# UVBoardFlippingGND.net
KiCad netlist of a schematic drawn in EAGLE
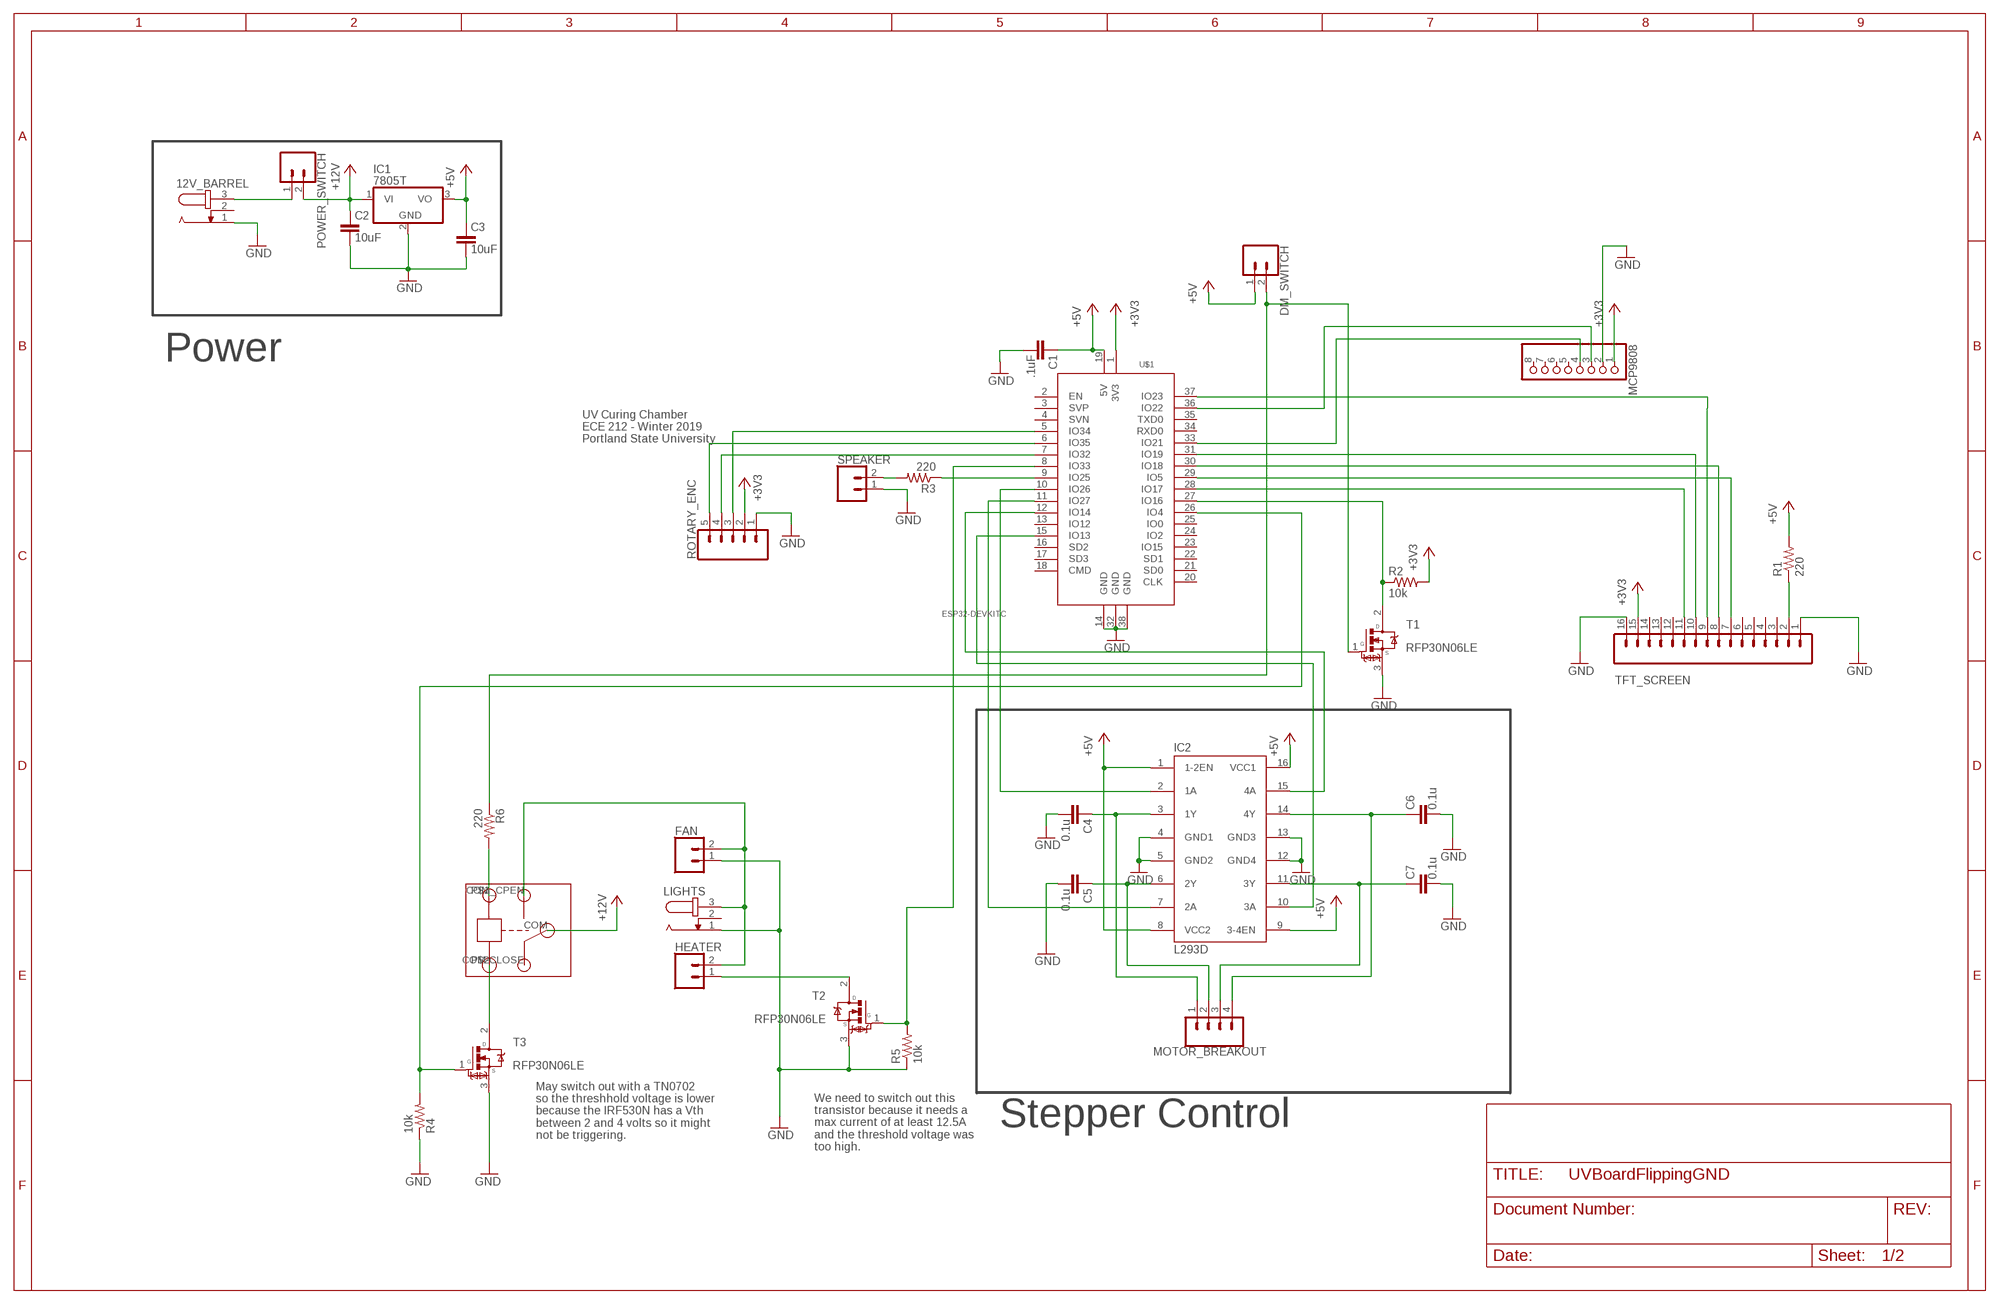
[diagram p0: schematic, sheet 1]

(export (version "E")
  (design (tool "Eeschema 10.0.6"))
  (components
    (comp (ref "12V_BARREL")
      (value "JACK-PLUG0")
      (footprint "eagle-import:SPC4077")
      (libsource (lib "eagle-import") (part "JACK-PLUG0"))
    )
    (comp (ref "C1")
      (value ".1uF")
      (footprint "eagle-import:C0603")
      (libsource (lib "eagle-import") (part "C-EUC0603"))
    )
    (comp (ref "C2")
      (value "10uF")
      (footprint "eagle-import:C1206")
      (libsource (lib "eagle-import") (part "C-EUC1206"))
    )
    (comp (ref "C3")
      (value "10uF")
      (footprint "eagle-import:C1206")
      (libsource (lib "eagle-import") (part "C-EUC1206"))
    )
    (comp (ref "C4")
      (value "0.1u")
      (footprint "eagle-import:C0603")
      (libsource (lib "eagle-import") (part "C-EUC0603"))
    )
    (comp (ref "C5")
      (value "0.1u")
      (footprint "eagle-import:C0603")
      (libsource (lib "eagle-import") (part "C-EUC0603"))
    )
    (comp (ref "C6")
      (value "0.1u")
      (footprint "eagle-import:C0603")
      (libsource (lib "eagle-import") (part "C-EUC0603"))
    )
    (comp (ref "C7")
      (value "0.1u")
      (footprint "eagle-import:C0603")
      (libsource (lib "eagle-import") (part "C-EUC0603"))
    )
    (comp (ref "DM_SWITCH")
      (value "CONN_025MM")
      (footprint "eagle-import:SCREWTERMINAL-5MM-2")
      (libsource (lib "eagle-import") (part "CONN_025MM"))
    )
    (comp (ref "FAN")
      (value "CONN_025MM")
      (footprint "eagle-import:SCREWTERMINAL-5MM-2")
      (libsource (lib "eagle-import") (part "CONN_025MM"))
    )
    (comp (ref "HEATER")
      (value "CONN_025MM")
      (footprint "eagle-import:SCREWTERMINAL-5MM-2")
      (libsource (lib "eagle-import") (part "CONN_025MM"))
    )
    (comp (ref "IC1")
      (value "7805T")
      (footprint "eagle-import:TO220H")
      (libsource (lib "eagle-import") (part "78T05"))
    )
    (comp (ref "IC2")
      (value "L293D")
      (footprint "eagle-import:DIL16")
      (libsource (lib "eagle-import") (part "L293D"))
    )
    (comp (ref "LIGHTS")
      (value "JACK-PLUG0")
      (footprint "eagle-import:SPC4077")
      (libsource (lib "eagle-import") (part "JACK-PLUG0"))
    )
    (comp (ref "MCP9808")
      (value "PINHD-1X8BIG")
      (footprint "eagle-import:1X08-BIG")
      (libsource (lib "eagle-import") (part "PINHD-1X8BIG"))
    )
    (comp (ref "MOTOR_BREAKOUT")
      (value "CONN_04SCREW")
      (footprint "eagle-import:SCREWTERMINAL-3.5MM-4")
      (libsource (lib "eagle-import") (part "CONN_04SCREW"))
    )
    (comp (ref "POWER_SWITCH")
      (value "CONN_025MM")
      (footprint "eagle-import:SCREWTERMINAL-5MM-2")
      (libsource (lib "eagle-import") (part "CONN_025MM"))
    )
    (comp (ref "R1")
      (value "220")
      (footprint "eagle-import:R0805")
      (libsource (lib "eagle-import") (part "R-US_R0805"))
    )
    (comp (ref "R2")
      (value "10k")
      (footprint "eagle-import:R0805")
      (libsource (lib "eagle-import") (part "R-US_R0805"))
    )
    (comp (ref "R3")
      (value "220")
      (footprint "eagle-import:R0805")
      (libsource (lib "eagle-import") (part "R-US_R0805"))
    )
    (comp (ref "R4")
      (value "10k")
      (footprint "eagle-import:R0805")
      (libsource (lib "eagle-import") (part "R-US_R0805"))
    )
    (comp (ref "R5")
      (value "10k")
      (footprint "eagle-import:R0805")
      (libsource (lib "eagle-import") (part "R-US_R0805"))
    )
    (comp (ref "R6")
      (value "220")
      (footprint "eagle-import:R0805")
      (libsource (lib "eagle-import") (part "R-US_R0805"))
    )
    (comp (ref "ROTARY_ENC")
      (value "CONN_05")
      (footprint "eagle-import:1X05")
      (libsource (lib "eagle-import") (part "CONN_05"))
    )
    (comp (ref "SPEAKER")
      (value "CONN_025MM")
      (footprint "eagle-import:SCREWTERMINAL-5MM-2")
      (libsource (lib "eagle-import") (part "CONN_025MM"))
    )
    (comp (ref "T1")
      (value "RFP30N06LE")
      (footprint "eagle-import:TRANS_RFP30N06LE")
      (fields (field (name "MF") "ON Semiconductor"))
      (libsource (lib "eagle-import") (part "RFP30N06LE"))
    )
    (comp (ref "T2")
      (value "RFP30N06LE")
      (footprint "eagle-import:TRANS_RFP30N06LE")
      (fields (field (name "MF") "ON Semiconductor"))
      (libsource (lib "eagle-import") (part "RFP30N06LE"))
    )
    (comp (ref "T3")
      (value "RFP30N06LE")
      (footprint "eagle-import:TRANS_RFP30N06LE")
      (fields (field (name "MF") "ON Semiconductor"))
      (libsource (lib "eagle-import") (part "RFP30N06LE"))
    )
    (comp (ref "TFT_SCREEN")
      (value "CONN_16")
      (footprint "eagle-import:1X16")
      (libsource (lib "eagle-import") (part "CONN_16"))
    )
    (comp (ref "U$1")
      (value "ESP32DEVKITC")
      (footprint "eagle-import:ESP32-DEVKITC")
      (libsource (lib "eagle-import") (part "ESP32DEVKITC"))
    )
    (comp (ref "U$2")
      (value "RELAY")
      (footprint "eagle-import:RELAY")
      (libsource (lib "eagle-import") (part "RELAY"))
    )
  )
  (nets
    (net (code "1") (name "+3V3") (class "Default")
      (node (ref "MCP9808") (pin "1") (pinfunction "1_1") (pintype "passive"))
      (node (ref "R2") (pin "2") (pinfunction "2_2") (pintype "passive"))
      (node (ref "ROTARY_ENC") (pin "2") (pinfunction "2_2") (pintype "passive"))
      (node (ref "TFT_SCREEN") (pin "15") (pinfunction "15_15") (pintype "passive"))
      (node (ref "U$1") (pin "1") (pinfunction "3V3_1") (pintype "bidirectional"))
    )
    (net (code "2") (name "+5V") (class "Default")
      (node (ref "C1") (pin "1") (pinfunction "1_1") (pintype "passive"))
      (node (ref "C3") (pin "1") (pinfunction "1_1") (pintype "passive"))
      (node (ref "DM_SWITCH") (pin "1") (pinfunction "1_1") (pintype "passive"))
      (node (ref "IC1") (pin "3") (pinfunction "VO_3") (pintype "passive"))
      (node (ref "IC2") (pin "1") (pinfunction "1-2EN_1") (pintype "input"))
      (node (ref "IC2") (pin "16") (pinfunction "VCC1_16") (pintype "power_in"))
      (node (ref "IC2") (pin "8") (pinfunction "VCC2_8") (pintype "power_in"))
      (node (ref "IC2") (pin "9") (pinfunction "3-4EN_9") (pintype "input"))
      (node (ref "R1") (pin "2") (pinfunction "2_2") (pintype "passive"))
      (node (ref "U$1") (pin "19") (pinfunction "5V_19") (pintype "bidirectional"))
    )
    (net (code "3") (name "ASDSFA") (class "Default")
      (node (ref "C2") (pin "1") (pinfunction "1_1") (pintype "passive"))
      (node (ref "IC1") (pin "1") (pinfunction "VI_1") (pintype "input"))
      (node (ref "POWER_SWITCH") (pin "2") (pinfunction "2_2") (pintype "passive"))
      (node (ref "U$2") (pin "COM") (pinfunction "COM_COM") (pintype "bidirectional"))
    )
    (net (code "4") (name "GND") (class "Default")
      (node (ref "12V_BARREL") (pin "1") (pinfunction "1_1") (pintype "passive"))
      (node (ref "C1") (pin "2") (pinfunction "2_2") (pintype "passive"))
      (node (ref "C2") (pin "2") (pinfunction "2_2") (pintype "passive"))
      (node (ref "C3") (pin "2") (pinfunction "2_2") (pintype "passive"))
      (node (ref "C4") (pin "2") (pinfunction "2_2") (pintype "passive"))
      (node (ref "C5") (pin "2") (pinfunction "2_2") (pintype "passive"))
      (node (ref "C6") (pin "2") (pinfunction "2_2") (pintype "passive"))
      (node (ref "C7") (pin "2") (pinfunction "2_2") (pintype "passive"))
      (node (ref "FAN") (pin "1") (pinfunction "1_1") (pintype "passive"))
      (node (ref "IC1") (pin "2") (pinfunction "GND_2") (pintype "passive"))
      (node (ref "IC2") (pin "12") (pinfunction "GND4_12") (pintype "power_in"))
      (node (ref "IC2") (pin "13") (pinfunction "GND3_13") (pintype "power_in"))
      (node (ref "IC2") (pin "4") (pinfunction "GND1_4") (pintype "power_in"))
      (node (ref "IC2") (pin "5") (pinfunction "GND2_5") (pintype "power_in"))
      (node (ref "LIGHTS") (pin "1") (pinfunction "1_1") (pintype "passive"))
      (node (ref "MCP9808") (pin "2") (pinfunction "2_2") (pintype "passive"))
      (node (ref "R4") (pin "1") (pinfunction "1_1") (pintype "passive"))
      (node (ref "R5") (pin "1") (pinfunction "1_1") (pintype "passive"))
      (node (ref "ROTARY_ENC") (pin "1") (pinfunction "1_1") (pintype "passive"))
      (node (ref "SPEAKER") (pin "1") (pinfunction "1_1") (pintype "passive"))
      (node (ref "T1") (pin "3") (pinfunction "S_3") (pintype "power_in"))
      (node (ref "T2") (pin "3") (pinfunction "S_3") (pintype "power_in"))
      (node (ref "T3") (pin "3") (pinfunction "S_3") (pintype "power_in"))
      (node (ref "TFT_SCREEN") (pin "1") (pinfunction "1_1") (pintype "passive"))
      (node (ref "TFT_SCREEN") (pin "16") (pinfunction "16_16") (pintype "passive"))
      (node (ref "U$1") (pin "14") (pinfunction "GND_14") (pintype "bidirectional"))
      (node (ref "U$1") (pin "32") (pinfunction "GND_32") (pintype "bidirectional"))
      (node (ref "U$1") (pin "38") (pinfunction "GND_38") (pintype "bidirectional"))
    )
    (net (code "5") (name "Net-(12V_BARREL-Pad3)") (class "Default")
      (node (ref "12V_BARREL") (pin "3") (pinfunction "3_3") (pintype "passive"))
      (node (ref "POWER_SWITCH") (pin "1") (pinfunction "1_1") (pintype "passive"))
    )
    (net (code "6") (name "Net-(IC2-1A)") (class "Default")
      (node (ref "IC2") (pin "2") (pinfunction "1A_2") (pintype "input"))
      (node (ref "U$1") (pin "10") (pinfunction "IO26_10") (pintype "bidirectional"))
    )
    (net (code "7") (name "Net-(IC2-1Y)") (class "Default")
      (node (ref "C4") (pin "1") (pinfunction "1_1") (pintype "passive"))
      (node (ref "IC2") (pin "3") (pinfunction "1Y_3") (pintype "output"))
      (node (ref "MOTOR_BREAKOUT") (pin "1") (pinfunction "1_1") (pintype "passive"))
    )
    (net (code "8") (name "Net-(IC2-2A)") (class "Default")
      (node (ref "IC2") (pin "7") (pinfunction "2A_7") (pintype "input"))
      (node (ref "U$1") (pin "11") (pinfunction "IO27_11") (pintype "bidirectional"))
    )
    (net (code "9") (name "Net-(IC2-2Y)") (class "Default")
      (node (ref "C5") (pin "1") (pinfunction "1_1") (pintype "passive"))
      (node (ref "IC2") (pin "6") (pinfunction "2Y_6") (pintype "output"))
      (node (ref "MOTOR_BREAKOUT") (pin "2") (pinfunction "2_2") (pintype "passive"))
    )
    (net (code "10") (name "Net-(IC2-3A)") (class "Default")
      (node (ref "IC2") (pin "10") (pinfunction "3A_10") (pintype "input"))
      (node (ref "U$1") (pin "15") (pinfunction "IO13_15") (pintype "bidirectional"))
    )
    (net (code "11") (name "Net-(IC2-3Y)") (class "Default")
      (node (ref "C7") (pin "1") (pinfunction "1_1") (pintype "passive"))
      (node (ref "IC2") (pin "11") (pinfunction "3Y_11") (pintype "output"))
      (node (ref "MOTOR_BREAKOUT") (pin "3") (pinfunction "3_3") (pintype "passive"))
    )
    (net (code "12") (name "Net-(IC2-4A)") (class "Default")
      (node (ref "IC2") (pin "15") (pinfunction "4A_15") (pintype "input"))
      (node (ref "U$1") (pin "12") (pinfunction "IO14_12") (pintype "bidirectional"))
    )
    (net (code "13") (name "Net-(IC2-4Y)") (class "Default")
      (node (ref "C6") (pin "1") (pinfunction "1_1") (pintype "passive"))
      (node (ref "IC2") (pin "14") (pinfunction "4Y_14") (pintype "output"))
      (node (ref "MOTOR_BREAKOUT") (pin "4") (pinfunction "4_4") (pintype "passive"))
    )
    (net (code "14") (name "Net-(R1-Pad1)") (class "Default")
      (node (ref "R1") (pin "1") (pinfunction "1_1") (pintype "passive"))
      (node (ref "TFT_SCREEN") (pin "2") (pinfunction "2_2") (pintype "passive"))
    )
    (net (code "15") (name "Net-(R3-Pad2)") (class "Default")
      (node (ref "R3") (pin "2") (pinfunction "2_2") (pintype "passive"))
      (node (ref "SPEAKER") (pin "2") (pinfunction "2_2") (pintype "passive"))
    )
    (net (code "16") (name "Net-(T1-D)") (class "Default")
      (node (ref "R2") (pin "1") (pinfunction "1_1") (pintype "passive"))
      (node (ref "T1") (pin "2") (pinfunction "D_2") (pintype "power_in"))
      (node (ref "U$1") (pin "27") (pinfunction "IO16_27") (pintype "bidirectional"))
    )
    (net (code "17") (name "Net-(T1-G)") (class "Default")
      (node (ref "DM_SWITCH") (pin "2") (pinfunction "2_2") (pintype "passive"))
      (node (ref "R6") (pin "1") (pinfunction "1_1") (pintype "passive"))
      (node (ref "T1") (pin "1") (pinfunction "G_1") (pintype "input"))
    )
    (net (code "18") (name "Net-(T2-D)") (class "Default")
      (node (ref "HEATER") (pin "1") (pinfunction "1_1") (pintype "passive"))
      (node (ref "T2") (pin "2") (pinfunction "D_2") (pintype "power_in"))
    )
    (net (code "19") (name "Net-(T2-G)") (class "Default")
      (node (ref "R5") (pin "2") (pinfunction "2_2") (pintype "passive"))
      (node (ref "T2") (pin "1") (pinfunction "G_1") (pintype "input"))
      (node (ref "U$1") (pin "8") (pinfunction "IO33_8") (pintype "bidirectional"))
    )
    (net (code "20") (name "Net-(T3-D)") (class "Default")
      (node (ref "T3") (pin "2") (pinfunction "D_2") (pintype "power_in"))
      (node (ref "U$2") (pin "P$2") (pinfunction "GND_P$2") (pintype "bidirectional"))
    )
    (net (code "21") (name "Net-(T3-G)") (class "Default")
      (node (ref "R4") (pin "2") (pinfunction "2_2") (pintype "passive"))
      (node (ref "T3") (pin "1") (pinfunction "G_1") (pintype "input"))
      (node (ref "U$1") (pin "26") (pinfunction "IO4_26") (pintype "bidirectional"))
    )
    (net (code "22") (name "Net-(U$1-IO5)") (class "Default")
      (node (ref "TFT_SCREEN") (pin "7") (pinfunction "7_7") (pintype "passive"))
      (node (ref "U$1") (pin "29") (pinfunction "IO5_29") (pintype "bidirectional"))
    )
    (net (code "23") (name "Net-(U$1-IO17)") (class "Default")
      (node (ref "TFT_SCREEN") (pin "11") (pinfunction "11_11") (pintype "passive"))
      (node (ref "U$1") (pin "28") (pinfunction "IO17_28") (pintype "bidirectional"))
    )
    (net (code "24") (name "Net-(U$1-IO18)") (class "Default")
      (node (ref "TFT_SCREEN") (pin "8") (pinfunction "8_8") (pintype "passive"))
      (node (ref "U$1") (pin "30") (pinfunction "IO18_30") (pintype "bidirectional"))
    )
    (net (code "25") (name "Net-(U$1-IO19)") (class "Default")
      (node (ref "TFT_SCREEN") (pin "10") (pinfunction "10_10") (pintype "passive"))
      (node (ref "U$1") (pin "31") (pinfunction "IO19_31") (pintype "bidirectional"))
    )
    (net (code "26") (name "Net-(U$1-IO21)") (class "Default")
      (node (ref "MCP9808") (pin "4") (pinfunction "4_4") (pintype "passive"))
      (node (ref "U$1") (pin "33") (pinfunction "IO21_33") (pintype "bidirectional"))
    )
    (net (code "27") (name "Net-(U$1-IO22)") (class "Default")
      (node (ref "MCP9808") (pin "3") (pinfunction "3_3") (pintype "passive"))
      (node (ref "U$1") (pin "36") (pinfunction "IO22_36") (pintype "bidirectional"))
    )
    (net (code "28") (name "Net-(U$1-IO23)") (class "Default")
      (node (ref "TFT_SCREEN") (pin "9") (pinfunction "9_9") (pintype "passive"))
      (node (ref "U$1") (pin "37") (pinfunction "IO23_37") (pintype "bidirectional"))
    )
    (net (code "29") (name "Net-(U$1-IO25)") (class "Default")
      (node (ref "R3") (pin "1") (pinfunction "1_1") (pintype "passive"))
      (node (ref "U$1") (pin "9") (pinfunction "IO25_9") (pintype "bidirectional"))
    )
    (net (code "30") (name "Net-(U$1-IO32)") (class "Default")
      (node (ref "ROTARY_ENC") (pin "4") (pinfunction "4_4") (pintype "passive"))
      (node (ref "U$1") (pin "7") (pinfunction "IO32_7") (pintype "bidirectional"))
    )
    (net (code "31") (name "Net-(U$1-IO34)") (class "Default")
      (node (ref "ROTARY_ENC") (pin "3") (pinfunction "3_3") (pintype "passive"))
      (node (ref "U$1") (pin "5") (pinfunction "IO34_5") (pintype "bidirectional"))
    )
    (net (code "32") (name "Net-(U$1-IO35)") (class "Default")
      (node (ref "ROTARY_ENC") (pin "5") (pinfunction "5_5") (pintype "passive"))
      (node (ref "U$1") (pin "6") (pinfunction "IO35_6") (pintype "bidirectional"))
    )
    (net (code "33") (name "Net-(U$2-COM-OPEN)") (class "Default")
      (node (ref "FAN") (pin "2") (pinfunction "2_2") (pintype "passive"))
      (node (ref "HEATER") (pin "2") (pinfunction "2_2") (pintype "passive"))
      (node (ref "LIGHTS") (pin "3") (pinfunction "3_3") (pintype "passive"))
      (node (ref "U$2") (pin "COM_CPEN") (pinfunction "COM-OPEN_COM_CPEN") (pintype "bidirectional"))
    )
    (net (code "34") (name "Net-(U$2-IN)") (class "Default")
      (node (ref "R6") (pin "2") (pinfunction "2_2") (pintype "passive"))
      (node (ref "U$2") (pin "P$1") (pinfunction "IN_P$1") (pintype "bidirectional"))
    )
    (net (code "35") (name "unconnected-(12V_BARREL-Pad2)") (class "Default")
      (node (ref "12V_BARREL") (pin "2") (pinfunction "2_2") (pintype "passive"))
    )
    (net (code "36") (name "unconnected-(LIGHTS-Pad2)") (class "Default")
      (node (ref "LIGHTS") (pin "2") (pinfunction "2_2") (pintype "passive"))
    )
    (net (code "37") (name "unconnected-(MCP9808-Pad5)") (class "Default")
      (node (ref "MCP9808") (pin "5") (pinfunction "5_5") (pintype "passive"))
    )
    (net (code "38") (name "unconnected-(MCP9808-Pad6)") (class "Default")
      (node (ref "MCP9808") (pin "6") (pinfunction "6_6") (pintype "passive"))
    )
    (net (code "39") (name "unconnected-(MCP9808-Pad7)") (class "Default")
      (node (ref "MCP9808") (pin "7") (pinfunction "7_7") (pintype "passive"))
    )
    (net (code "40") (name "unconnected-(MCP9808-Pad8)") (class "Default")
      (node (ref "MCP9808") (pin "8") (pinfunction "8_8") (pintype "passive"))
    )
    (net (code "41") (name "unconnected-(TFT_SCREEN-Pad3)") (class "Default")
      (node (ref "TFT_SCREEN") (pin "3") (pinfunction "3_3") (pintype "passive"))
    )
    (net (code "42") (name "unconnected-(TFT_SCREEN-Pad4)") (class "Default")
      (node (ref "TFT_SCREEN") (pin "4") (pinfunction "4_4") (pintype "passive"))
    )
    (net (code "43") (name "unconnected-(TFT_SCREEN-Pad5)") (class "Default")
      (node (ref "TFT_SCREEN") (pin "5") (pinfunction "5_5") (pintype "passive"))
    )
    (net (code "44") (name "unconnected-(TFT_SCREEN-Pad6)") (class "Default")
      (node (ref "TFT_SCREEN") (pin "6") (pinfunction "6_6") (pintype "passive"))
    )
    (net (code "45") (name "unconnected-(TFT_SCREEN-Pad12)") (class "Default")
      (node (ref "TFT_SCREEN") (pin "12") (pinfunction "12_12") (pintype "passive"))
    )
    (net (code "46") (name "unconnected-(TFT_SCREEN-Pad13)") (class "Default")
      (node (ref "TFT_SCREEN") (pin "13") (pinfunction "13_13") (pintype "passive"))
    )
    (net (code "47") (name "unconnected-(TFT_SCREEN-Pad14)") (class "Default")
      (node (ref "TFT_SCREEN") (pin "14") (pinfunction "14_14") (pintype "passive"))
    )
    (net (code "48") (name "unconnected-(U$1-CLK-Pad20)") (class "Default")
      (node (ref "U$1") (pin "20") (pinfunction "CLK_20") (pintype "bidirectional"))
    )
    (net (code "49") (name "unconnected-(U$1-CMD-Pad18)") (class "Default")
      (node (ref "U$1") (pin "18") (pinfunction "CMD_18") (pintype "bidirectional"))
    )
    (net (code "50") (name "unconnected-(U$1-EN-Pad2)") (class "Default")
      (node (ref "U$1") (pin "2") (pinfunction "EN_2") (pintype "bidirectional"))
    )
    (net (code "51") (name "unconnected-(U$1-IO0-Pad25)") (class "Default")
      (node (ref "U$1") (pin "25") (pinfunction "IO0_25") (pintype "bidirectional"))
    )
    (net (code "52") (name "unconnected-(U$1-IO2-Pad24)") (class "Default")
      (node (ref "U$1") (pin "24") (pinfunction "IO2_24") (pintype "bidirectional"))
    )
    (net (code "53") (name "unconnected-(U$1-IO12-Pad13)") (class "Default")
      (node (ref "U$1") (pin "13") (pinfunction "IO12_13") (pintype "bidirectional"))
    )
    (net (code "54") (name "unconnected-(U$1-IO15-Pad23)") (class "Default")
      (node (ref "U$1") (pin "23") (pinfunction "IO15_23") (pintype "bidirectional"))
    )
    (net (code "55") (name "unconnected-(U$1-RXD0-Pad34)") (class "Default")
      (node (ref "U$1") (pin "34") (pinfunction "RXD0_34") (pintype "bidirectional"))
    )
    (net (code "56") (name "unconnected-(U$1-SD0-Pad21)") (class "Default")
      (node (ref "U$1") (pin "21") (pinfunction "SD0_21") (pintype "bidirectional"))
    )
    (net (code "57") (name "unconnected-(U$1-SD1-Pad22)") (class "Default")
      (node (ref "U$1") (pin "22") (pinfunction "SD1_22") (pintype "bidirectional"))
    )
    (net (code "58") (name "unconnected-(U$1-SD2-Pad16)") (class "Default")
      (node (ref "U$1") (pin "16") (pinfunction "SD2_16") (pintype "bidirectional"))
    )
    (net (code "59") (name "unconnected-(U$1-SD3-Pad17)") (class "Default")
      (node (ref "U$1") (pin "17") (pinfunction "SD3_17") (pintype "bidirectional"))
    )
    (net (code "60") (name "unconnected-(U$1-SVN-Pad4)") (class "Default")
      (node (ref "U$1") (pin "4") (pinfunction "SVN_4") (pintype "bidirectional"))
    )
    (net (code "61") (name "unconnected-(U$1-SVP-Pad3)") (class "Default")
      (node (ref "U$1") (pin "3") (pinfunction "SVP_3") (pintype "bidirectional"))
    )
    (net (code "62") (name "unconnected-(U$1-TXD0-Pad35)") (class "Default")
      (node (ref "U$1") (pin "35") (pinfunction "TXD0_35") (pintype "bidirectional"))
    )
    (net (code "63") (name "unconnected-(U$2-PadCOM-CLOSE)") (class "Default")
      (node (ref "U$2") (pin "COM-CLOSE") (pinfunction "COM-CLOSE_COM-CLOSE") (pintype "bidirectional"))
    )
  )
)
